# MC_Sch2.net
KiCad netlist of a schematic drawn in Altium Designer
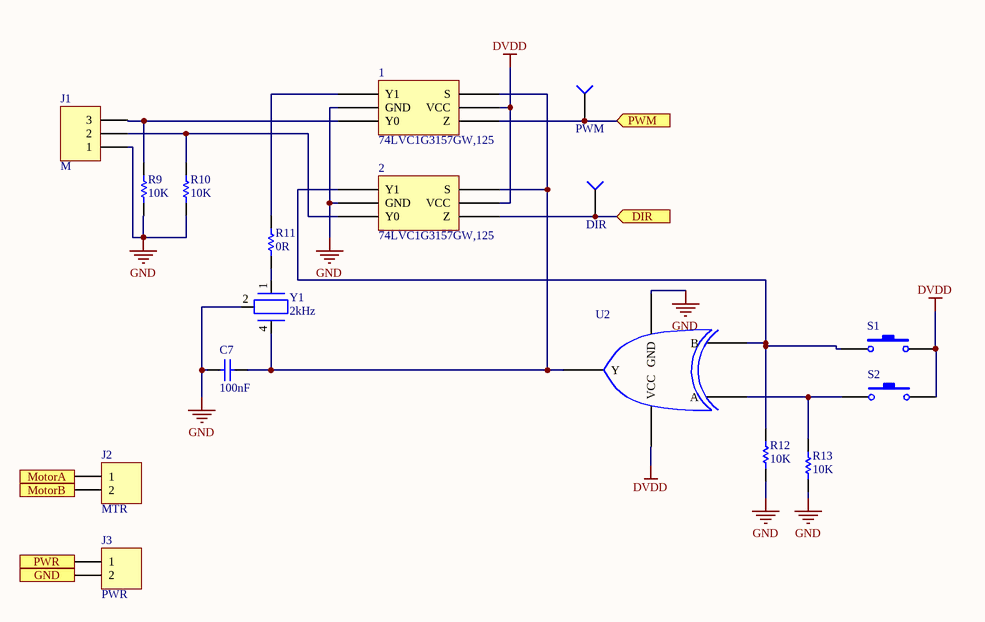
[diagram p0: MC_Sch2.SchDoc]

(export (version "E")
  (design (tool "Eeschema 10.0.6"))
  (components
    (comp (ref "1")
      (value "74LVC1G3157GW,125")
      (footprint "IC MUX/DEMUX")
      (fields (field (name "MANUFACTURER") "NXP Semiconductors"))
      (libsource (lib "UWRT_Schematic_Library_2019") (part "IC MUX/DEMUX 2x1"))
    )
    (comp (ref "2")
      (value "74LVC1G3157GW,125")
      (footprint "IC MUX/DEMUX")
      (fields (field (name "MANUFACTURER") "NXP Semiconductors"))
      (libsource (lib "UWRT_Schematic_Library_2019") (part "IC MUX/DEMUX 2x1"))
    )
    (comp (ref "C7")
      (value "100nF")
      (footprint "CAPC0603(1608)55_N")
      (description "CAP CER 10000PF 16V X7R 0603")
      (fields (field (name "MPN") "CC0603KRX7R7BB103") (field (name "MANUFACTURER") "Yageo"))
      (libsource (lib "UWRT_Schematic_Library_2019") (part "CAP_10nF_0603"))
    )
    (comp (ref "J1")
      (value "M")
      (footprint "HDR1X3")
      (description "Header, 3-Pin")
      (fields (field (name "PUBLISHER") "Altium Limited"))
      (libsource (lib "Miscellaneous Connectors") (part "Header 3"))
    )
    (comp (ref "J2")
      (value "MTR")
      (footprint "OSTYK51102030")
      (description "Header, 2-Pin")
      (fields (field (name "PUBLISHER") "Altium Limited"))
      (libsource (lib "UWRT_Schematic_Library_2019") (part "TERMINAL_2"))
    )
    (comp (ref "J3")
      (value "PWR")
      (footprint "OSTYK51102030")
      (description "Header, 2-Pin")
      (fields (field (name "PUBLISHER") "Altium Limited"))
      (libsource (lib "UWRT_Schematic_Library_2019") (part "TERMINAL_2"))
    )
    (comp (ref "R9")
      (value "10K")
      (footprint "RESC0603(1608)_N")
      (description "RES SMD 10K OHM 5% 1/10W 0603")
      (fields (field (name "MANUFACTURER") "Yageo") (field (name "MPN") "RC0603JR-0710KL"))
      (libsource (lib "UWRT_Schematic_Library_2019") (part "RES_10K_0603"))
    )
    (comp (ref "R10")
      (value "10K")
      (footprint "RESC0603(1608)_N")
      (description "RES SMD 10K OHM 5% 1/10W 0603")
      (fields (field (name "MANUFACTURER") "Yageo") (field (name "MPN") "RC0603JR-0710KL"))
      (libsource (lib "UWRT_Schematic_Library_2019") (part "RES_10K_0603"))
    )
    (comp (ref "R11")
      (value "0R")
      (footprint "RESC0603(1608)_N")
      (description "RES SMD 0 OHM JUMPER 1/10W 0603")
      (fields (field (name "MANUFACTURER") "Yageo") (field (name "MPN") "RC0603JR-070RL"))
      (libsource (lib "UWRT_Schematic_Library_2019") (part "RES_0R_0603"))
    )
    (comp (ref "R12")
      (value "10K")
      (footprint "RESC0603(1608)_N")
      (description "RES SMD 10K OHM 5% 1/10W 0603")
      (fields (field (name "MANUFACTURER") "Yageo") (field (name "MPN") "RC0603JR-0710KL"))
      (libsource (lib "UWRT_Schematic_Library_2019") (part "RES_10K_0603"))
    )
    (comp (ref "R13")
      (value "10K")
      (footprint "RESC0603(1608)_N")
      (description "RES SMD 10K OHM 5% 1/10W 0603")
      (fields (field (name "MANUFACTURER") "Yageo") (field (name "MPN") "RC0603JR-0710KL"))
      (libsource (lib "UWRT_Schematic_Library_2019") (part "RES_10K_0603"))
    )
    (comp (ref "S1")
      (value "SW_PWR")
      (footprint "PTS830GM140")
      (description "Power Switch (Red)")
      (fields
        (field (name "MPN") "PTS830GM140 SMTR LFS")
        (field (name "DIGIKEY PART NUMBER") "CKN10587CT-ND")
      )
      (libsource (lib "UWRT_Schematic_Library_2019") (part "SW_PWR"))
    )
    (comp (ref "S2")
      (value "SW_PWR")
      (footprint "PTS830GM140")
      (description "Power Switch (Red)")
      (fields
        (field (name "MPN") "PTS830GM140 SMTR LFS")
        (field (name "DIGIKEY PART NUMBER") "CKN10587CT-ND")
      )
      (libsource (lib "UWRT_Schematic_Library_2019") (part "SW_PWR"))
    )
    (comp (ref "TP5")
      (value "PWM")
      (footprint "TESTPOINT_LOOP")
      (description "TESTPOINT_SMD")
      (libsource (lib "UWRT_Schematic_Library_2019") (part "*"))
    )
    (comp (ref "TP6")
      (value "DIR")
      (footprint "TESTPOINT_LOOP")
      (description "TESTPOINT_SMD")
      (libsource (lib "UWRT_Schematic_Library_2019") (part "*"))
    )
    (comp (ref "U2")
      (value "SN74AHC1G02DBVT")
      (footprint "SOT23-5")
      (fields (field (name "MANUFACTURER") "Texas Instruments"))
      (libsource (lib "UWRT_Schematic_Library_2019") (part "IC GATE XOR"))
    )
    (comp (ref "Y1")
      (value "2kHz")
      (footprint "CDFN-4")
      (description "OSCILLATOR_2kHz")
      (libsource (lib "UWRT_Schematic_Library_2019") (part "OSC_2kHz"))
    )
  )
  (nets
    (net (code "1") (name "/DIR") (class "Default")
      (node (ref "2") (pin "4") (pinfunction "Z_4") (pintype "passive"))
      (node (ref "TP6") (pin "1") (pinfunction "=value_1") (pintype "passive"))
    )
    (net (code "2") (name "/MotorA") (class "Default")
      (node (ref "J2") (pin "1") (pinfunction "1_1") (pintype "passive"))
    )
    (net (code "3") (name "/MotorB") (class "Default")
      (node (ref "J2") (pin "2") (pinfunction "2_2") (pintype "passive"))
    )
    (net (code "4") (name "/PWM") (class "Default")
      (node (ref "1") (pin "4") (pinfunction "Z_4") (pintype "passive"))
      (node (ref "TP5") (pin "1") (pinfunction "=value_1") (pintype "passive"))
    )
    (net (code "5") (name "/PWR") (class "Default")
      (node (ref "J3") (pin "1") (pinfunction "1_1") (pintype "passive"))
    )
    (net (code "6") (name "DVDD") (class "Default")
      (node (ref "1") (pin "5") (pinfunction "VCC_5") (pintype "passive"))
      (node (ref "2") (pin "5") (pinfunction "VCC_5") (pintype "passive"))
      (node (ref "S1") (pin "2") (pinfunction "2_2") (pintype "passive"))
      (node (ref "S2") (pin "2") (pinfunction "2_2") (pintype "passive"))
      (node (ref "U2") (pin "5") (pinfunction "VCC_5") (pintype "passive"))
    )
    (net (code "7") (name "GND") (class "Default")
      (node (ref "1") (pin "2") (pinfunction "GND_2") (pintype "passive"))
      (node (ref "2") (pin "2") (pinfunction "GND_2") (pintype "passive"))
      (node (ref "C7") (pin "2") (pinfunction "2_2") (pintype "passive"))
      (node (ref "J1") (pin "1") (pinfunction "1_1") (pintype "passive"))
      (node (ref "J3") (pin "2") (pinfunction "2_2") (pintype "passive"))
      (node (ref "R10") (pin "1") (pinfunction "1_1") (pintype "passive"))
      (node (ref "R12") (pin "1") (pinfunction "1_1") (pintype "passive"))
      (node (ref "R13") (pin "1") (pinfunction "1_1") (pintype "passive"))
      (node (ref "R9") (pin "1") (pinfunction "1_1") (pintype "passive"))
      (node (ref "U2") (pin "3") (pinfunction "GND_3") (pintype "passive"))
      (node (ref "Y1") (pin "2") (pinfunction "GND_2") (pintype "passive"))
    )
    (net (code "8") (name "Net-(1-S)") (class "Default")
      (node (ref "1") (pin "6") (pinfunction "S_6") (pintype "passive"))
      (node (ref "2") (pin "6") (pinfunction "S_6") (pintype "passive"))
      (node (ref "C7") (pin "1") (pinfunction "1_1") (pintype "passive"))
      (node (ref "U2") (pin "4") (pinfunction "Y_4") (pintype "passive"))
      (node (ref "Y1") (pin "4") (pinfunction "VDD_4") (pintype "passive"))
    )
    (net (code "9") (name "Net-(1-Y0)") (class "Default")
      (node (ref "1") (pin "3") (pinfunction "Y0_3") (pintype "passive"))
      (node (ref "J1") (pin "3") (pinfunction "3_3") (pintype "passive"))
      (node (ref "R9") (pin "2") (pinfunction "2_2") (pintype "passive"))
    )
    (net (code "10") (name "Net-(1-Y1)") (class "Default")
      (node (ref "1") (pin "1") (pinfunction "Y1_1") (pintype "passive"))
      (node (ref "R11") (pin "2") (pinfunction "2_2") (pintype "passive"))
    )
    (net (code "11") (name "Net-(2-Y0)") (class "Default")
      (node (ref "2") (pin "3") (pinfunction "Y0_3") (pintype "passive"))
      (node (ref "J1") (pin "2") (pinfunction "2_2") (pintype "passive"))
      (node (ref "R10") (pin "2") (pinfunction "2_2") (pintype "passive"))
    )
    (net (code "12") (name "Net-(2-Y1)") (class "Default")
      (node (ref "2") (pin "1") (pinfunction "Y1_1") (pintype "passive"))
      (node (ref "R12") (pin "2") (pinfunction "2_2") (pintype "passive"))
      (node (ref "S1") (pin "1") (pinfunction "1_1") (pintype "passive"))
      (node (ref "U2") (pin "2") (pinfunction "B_2") (pintype "passive"))
    )
    (net (code "13") (name "Net-(U2-A)") (class "Default")
      (node (ref "R13") (pin "2") (pinfunction "2_2") (pintype "passive"))
      (node (ref "S2") (pin "1") (pinfunction "1_1") (pintype "passive"))
      (node (ref "U2") (pin "1") (pinfunction "A_1") (pintype "passive"))
    )
    (net (code "14") (name "Net-(Y1-OUT)") (class "Default")
      (node (ref "R11") (pin "1") (pinfunction "1_1") (pintype "passive"))
      (node (ref "Y1") (pin "1") (pinfunction "OUT_1") (pintype "passive"))
    )
  )
)
